# Monostable_generator_PIC10_L_F322.net
KiCad netlist of a schematic drawn in Altium Designer
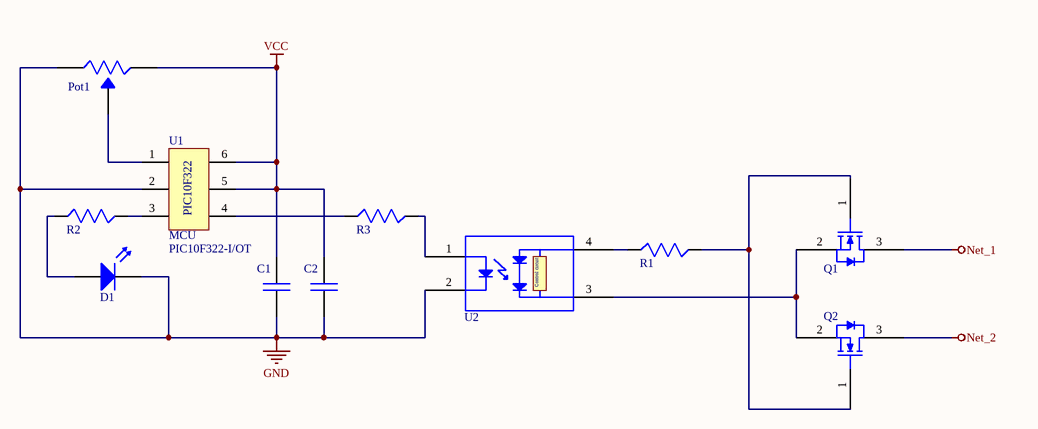
[diagram p0: Monostable_generator_PIC10(L)F322.SchDoc]

(export (version "E")
  (design (tool "Eeschema 10.0.6"))
  (components
    (comp (ref "C1")
      (value "C0805C104M3RACTU")
      (footprint "Generator_monostabilny:Capacitor")
      (description "CAP CER 0.1UF 25V X7R 0805")
      (fields (field (name "TOLERANCE") "20%") (field (name "VOLTAGE") "25V"))
      (libsource (lib "Generator_monostabilny") (part "C0805C104M3RACTU"))
    )
    (comp (ref "C2")
      (value "C0805C104M3RACTU")
      (footprint "Generator_monostabilny:Capacitor")
      (description "CAP CER 0.1UF 25V X7R 0805")
      (fields (field (name "TOLERANCE") "20%") (field (name "VOLTAGE") "25V"))
      (libsource (lib "Generator_monostabilny") (part "C0805C104M3RACTU"))
    )
    (comp (ref "D1")
      (value "LED")
      (footprint "Generator_monostabilny:Diode")
      (description "LED; SMD; 0603; orange; 100-200mcd; 1.6x0.8mm; 120°; 5m")
      (fields
        (field (name "MANUFACTURER") "OptoSupply")
        (field (name "MANUFACTURER PART NUMBER") "OSO50603C1E")
      )
      (libsource (lib "Generator_monostabilny") (part "OSO50603C1E"))
    )
    (comp (ref "Pot1")
      (value "3305SMD")
      (footprint "CA6XVSMD")
      (libsource (lib "Generator_monostabilny") (part "3305SMD"))
    )
    (comp (ref "Q1")
      (value "BSS205NH6327")
      (footprint "Generator_monostabilny:SOT95P250X110-3N")
      (description "Single N-Channel 20 V 50 mOhm 2.1 nC OptiMOS? Small Signal Mosfet - SOT-23")
      (fields (field (name "MANUFACTURER") "Infineon"))
      (libsource (lib "Generator_monostabilny") (part "BSS205NH6327"))
    )
    (comp (ref "Q2")
      (value "BSS205NH6327")
      (footprint "Generator_monostabilny:SOT95P250X110-3N")
      (description "Single N-Channel 20 V 50 mOhm 2.1 nC OptiMOS? Small Signal Mosfet - SOT-23")
      (fields (field (name "MANUFACTURER") "Infineon"))
      (libsource (lib "Generator_monostabilny") (part "BSS205NH6327"))
    )
    (comp (ref "R1")
      (value "SWR1206-24R-5%")
      (footprint "Generator_monostabilny:Resistor")
      (libsource (lib "Generator_monostabilny") (part "SWR1206-24R-5%"))
    )
    (comp (ref "R2")
      (value "SWR1206-24R-5%")
      (footprint "Generator_monostabilny:Resistor")
      (libsource (lib "Generator_monostabilny") (part "SWR1206-24R-5%"))
    )
    (comp (ref "R3")
      (value "SWR1206-24R-5%")
      (footprint "Generator_monostabilny:Resistor")
      (libsource (lib "Generator_monostabilny") (part "SWR1206-24R-5%"))
    )
    (comp (ref "U1")
      (value "MCU")
      (footprint "Generator_monostabilny:SOT95P270X145-6N")
      (description "RISC Microcontroller, 8-Bit, FLASH, PIC10 CPU, 20MHz, CMOS, PDSO6")
      (fields
        (field (name "SUPPLIER PART NUMBER 1") "PIC10F322-I/OT")
        (field (name "MANUFACTURER") "Microchip")
        (field (name "MANUFACTURER PART NUMBER") "PIC10F322-I/OT")
      )
      (libsource (lib "Generator_monostabilny") (part "PIC10F322-I/OT"))
    )
    (comp (ref "U2")
      (value "APV2121S")
      (footprint "Generator_monostabilny:SOP254P680X210-4N")
      (description "Photovoltaic MOSFET Driver , 4-pin SOP,")
      (fields (field (name "MANUFACTURER") "Panasonic"))
      (libsource (lib "Generator_monostabilny") (part "APV2121S"))
    )
  )
  (nets
    (net (code "1") (name "GND") (class "Default")
      (node (ref "C1") (pin "1") (pinfunction "1_1") (pintype "passive"))
      (node (ref "C2") (pin "1") (pinfunction "1_1") (pintype "passive"))
      (node (ref "D1") (pin "K") (pinfunction "K_K") (pintype "passive"))
      (node (ref "Pot1") (pin "1") (pinfunction "1_1") (pintype "passive"))
      (node (ref "U1") (pin "2") (pinfunction "2_2") (pintype "passive"))
      (node (ref "U2") (pin "2") (pinfunction "2_2") (pintype "passive"))
    )
    (net (code "2") (name "Net-(D1-PadA)") (class "Default")
      (node (ref "D1") (pin "A") (pinfunction "A_A") (pintype "passive"))
      (node (ref "R2") (pin "1") (pinfunction "1_1") (pintype "passive"))
    )
    (net (code "3") (name "Net-(Pot1-Pad2)") (class "Default")
      (node (ref "Pot1") (pin "2") (pinfunction "2_2") (pintype "passive"))
      (node (ref "U1") (pin "1") (pinfunction "1_1") (pintype "passive"))
    )
    (net (code "4") (name "Net-(Q1-Pad1)") (class "Default")
      (node (ref "Q1") (pin "1") (pinfunction "1_1") (pintype "passive"))
      (node (ref "Q2") (pin "1") (pinfunction "1_1") (pintype "passive"))
      (node (ref "R1") (pin "1") (pinfunction "1_1") (pintype "passive"))
    )
    (net (code "5") (name "Net-(Q1-Pad2)") (class "Default")
      (node (ref "Q1") (pin "2") (pinfunction "2_2") (pintype "passive"))
      (node (ref "Q2") (pin "2") (pinfunction "2_2") (pintype "passive"))
      (node (ref "U2") (pin "3") (pinfunction "3_3") (pintype "passive"))
    )
    (net (code "6") (name "Net-(R1-15)") (class "Default")
      (node (ref "R1") (pin "2") (pinfunction "15_2") (pintype "passive"))
      (node (ref "U2") (pin "4") (pinfunction "4_4") (pintype "passive"))
    )
    (net (code "7") (name "Net-(R2-15)") (class "Default")
      (node (ref "R2") (pin "2") (pinfunction "15_2") (pintype "passive"))
      (node (ref "U1") (pin "3") (pinfunction "3_3") (pintype "passive"))
    )
    (net (code "8") (name "Net-(R3-15)") (class "Default")
      (node (ref "R3") (pin "2") (pinfunction "15_2") (pintype "passive"))
      (node (ref "U2") (pin "1") (pinfunction "1_1") (pintype "passive"))
    )
    (net (code "9") (name "Net-(R3-Pad1)") (class "Default")
      (node (ref "R3") (pin "1") (pinfunction "1_1") (pintype "passive"))
      (node (ref "U1") (pin "4") (pinfunction "4_4") (pintype "passive"))
    )
    (net (code "10") (name "Net_1") (class "Default")
      (node (ref "Q1") (pin "3") (pinfunction "3_3") (pintype "passive"))
    )
    (net (code "11") (name "Net_2") (class "Default")
      (node (ref "Q2") (pin "3") (pinfunction "3_3") (pintype "passive"))
    )
    (net (code "12") (name "VCC") (class "Default")
      (node (ref "C1") (pin "2") (pinfunction "2_2") (pintype "passive"))
      (node (ref "C2") (pin "2") (pinfunction "2_2") (pintype "passive"))
      (node (ref "Pot1") (pin "3") (pinfunction "3_3") (pintype "passive"))
      (node (ref "U1") (pin "5") (pinfunction "5_5") (pintype "passive"))
      (node (ref "U1") (pin "6") (pinfunction "6_6") (pintype "passive"))
    )
  )
)
